# Sheet2.net
KiCad netlist of a schematic drawn in Altium Designer
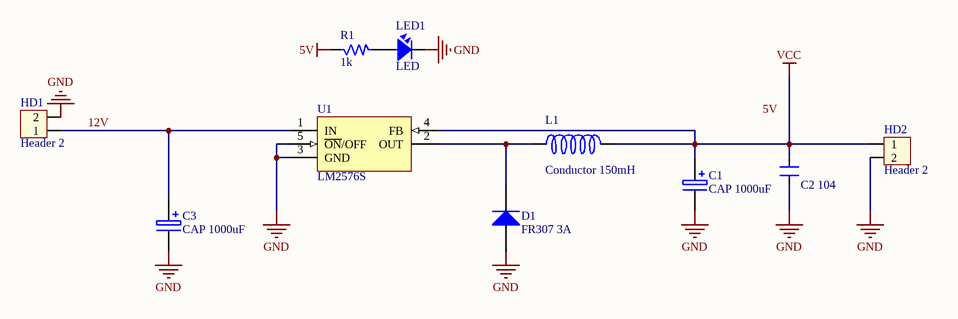
[diagram p0: Sheet2.SchDoc]

(export (version "E")
  (design (tool "Eeschema 10.0.6"))
  (components
    (comp (ref "C1")
      (value "CAP 1000uF")
      (footprint "CP2/4")
      (description "Cap")
      (libsource (lib "My library altium") (part "CAP hoa"))
    )
    (comp (ref "C2 104")
      (value "CAP gom")
      (footprint "CN3")
      (libsource (lib "My library altium") (part "CAP gom"))
    )
    (comp (ref "C3")
      (value "CAP 1000uF")
      (footprint "CP2/4")
      (description "Cap")
      (libsource (lib "My library altium") (part "CAP hoa"))
    )
    (comp (ref "D1")
      (value "FR307 3A")
      (footprint "DIODE/POW/3A")
      (description "Diode Power")
      (fields (field (name "PUBLISHER") "Altium Limited"))
      (libsource (lib "My library altium") (part "Diode Power 3A"))
    )
    (comp (ref "HD1")
      (value "Header 2")
      (footprint "HED2")
      (description "Header 2 (Green)")
      (libsource (lib "My library altium") (part "Header 2"))
    )
    (comp (ref "HD2")
      (value "Header 2")
      (footprint "HED2")
      (description "Header 2 (Green)")
      (libsource (lib "") (part "Header 2_1"))
    )
    (comp (ref "L1")
      (value "Conductor 150mH")
      (footprint "CUON CAM 200mil")
      (libsource (lib "My library altium") (part "Conductor"))
    )
    (comp (ref "LED1")
      (value "LED")
      (footprint "LED-3")
      (description "LED Single colour Green and Red")
      (libsource (lib "syhaunguyen") (part "LED"))
    )
    (comp (ref "R1")
      (value "1k")
      (footprint "R1/4W")
      (description "Resistor 1/4W")
      (libsource (lib "syhaunguyen") (part "R"))
    )
    (comp (ref "U1")
      (value "LM2576S")
      (footprint "LM2576t")
      (description "Simple Switcher 3A Step Down Voltage Regulator")
      (fields (field (name "PUBLISHER") "Altium Limited"))
      (libsource (lib "My library altium") (part "LM2576S"))
    )
  )
  (nets
    (net (code "1") (name "/12V") (class "Default")
      (node (ref "C3") (pin "1") (pintype "passive"))
      (node (ref "HD1") (pin "1") (pinfunction "1_1") (pintype "passive"))
      (node (ref "U1") (pin "1") (pinfunction "IN_1") (pintype "power_in"))
    )
    (net (code "2") (name "5V") (class "Default")
      (node (ref "R1") (pin "1") (pinfunction "1_1") (pintype "passive"))
    )
    (net (code "3") (name "GND") (class "Default")
      (node (ref "C1") (pin "2") (pintype "passive"))
      (node (ref "C2 104") (pin "1") (pinfunction "1_1") (pintype "passive"))
      (node (ref "C3") (pin "2") (pintype "passive"))
      (node (ref "D1") (pin "1") (pinfunction "A_1") (pintype "passive"))
      (node (ref "HD1") (pin "2") (pinfunction "2_2") (pintype "passive"))
      (node (ref "HD2") (pin "2") (pinfunction "2_2") (pintype "passive"))
      (node (ref "LED1") (pin "2") (pinfunction "2_2") (pintype "passive"))
      (node (ref "U1") (pin "3") (pinfunction "GND_3") (pintype "power_in"))
      (node (ref "U1") (pin "5") (pinfunction "~{ON}/OFF_5") (pintype "input"))
    )
    (net (code "4") (name "Net-(D1-K)") (class "Default")
      (node (ref "D1") (pin "2") (pinfunction "K_2") (pintype "passive"))
      (node (ref "L1") (pin "1") (pinfunction "1_1") (pintype "passive"))
      (node (ref "U1") (pin "2") (pinfunction "OUT_2") (pintype "power_in"))
    )
    (net (code "5") (name "Net-(LED1-Pad1)") (class "Default")
      (node (ref "LED1") (pin "1") (pinfunction "1_1") (pintype "passive"))
      (node (ref "R1") (pin "2") (pinfunction "2_2") (pintype "passive"))
    )
    (net (code "6") (name "VCC") (class "Default")
      (node (ref "C1") (pin "1") (pintype "passive"))
      (node (ref "C2 104") (pin "2") (pinfunction "2_2") (pintype "passive"))
      (node (ref "HD2") (pin "1") (pinfunction "1_1") (pintype "passive"))
      (node (ref "L1") (pin "2") (pinfunction "2_2") (pintype "passive"))
      (node (ref "U1") (pin "4") (pinfunction "FB_4") (pintype "input"))
    )
  )
)
